# TIA2_4ch.net
KiCad netlist of a schematic drawn in EAGLE
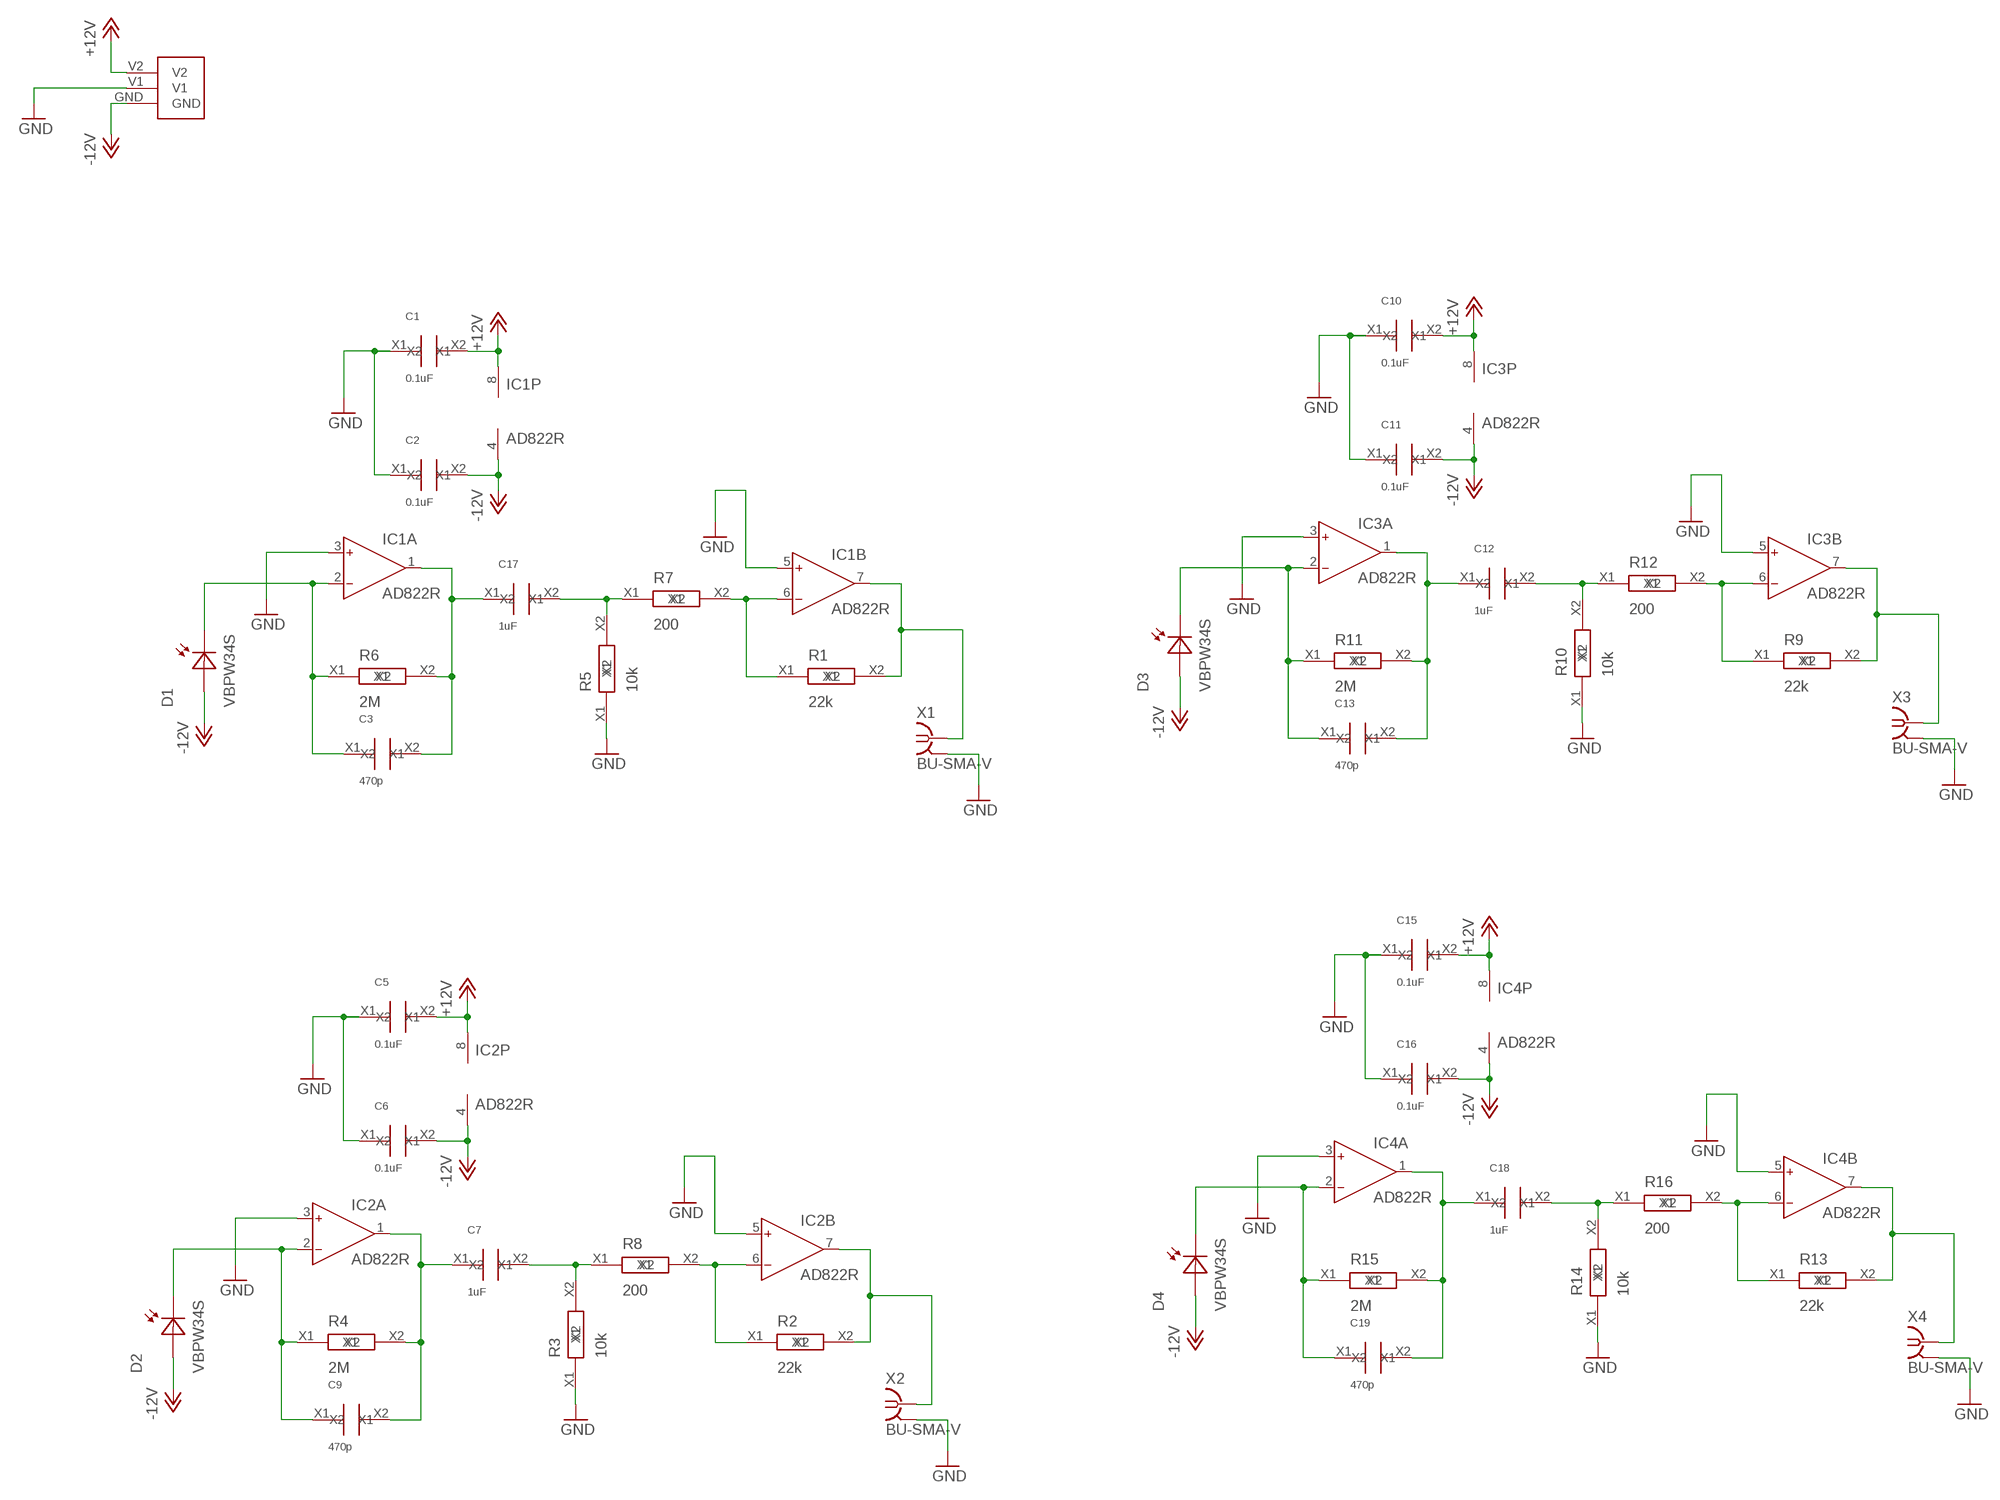
[diagram p0: schematic, sheet 1]

(export (version "E")
  (design (tool "Eeschema 10.0.6"))
  (components
    (comp (ref "C1")
      (value "0.1uF")
      (footprint "eagle-import:SMD_2.1X1.25")
      (libsource (lib "eagle-import") (part "C_SMD_2.1X1.25"))
    )
    (comp (ref "C2")
      (value "0.1uF")
      (footprint "eagle-import:SMD_2.1X1.25")
      (libsource (lib "eagle-import") (part "C_SMD_2.1X1.25"))
    )
    (comp (ref "C3")
      (value "470p")
      (footprint "eagle-import:SMD_2.1X1.25")
      (libsource (lib "eagle-import") (part "C_SMD_2.1X1.25"))
    )
    (comp (ref "C5")
      (value "0.1uF")
      (footprint "eagle-import:SMD_2.1X1.25")
      (libsource (lib "eagle-import") (part "C_SMD_2.1X1.25"))
    )
    (comp (ref "C6")
      (value "0.1uF")
      (footprint "eagle-import:SMD_2.1X1.25")
      (libsource (lib "eagle-import") (part "C_SMD_2.1X1.25"))
    )
    (comp (ref "C7")
      (value "1uF")
      (footprint "eagle-import:SMD_2.1X1.25")
      (libsource (lib "eagle-import") (part "C_SMD_2.1X1.25"))
    )
    (comp (ref "C9")
      (value "470p")
      (footprint "eagle-import:SMD_2.1X1.25")
      (libsource (lib "eagle-import") (part "C_SMD_2.1X1.25"))
    )
    (comp (ref "C10")
      (value "0.1uF")
      (footprint "eagle-import:SMD_2.1X1.25")
      (libsource (lib "eagle-import") (part "C_SMD_2.1X1.25"))
    )
    (comp (ref "C11")
      (value "0.1uF")
      (footprint "eagle-import:SMD_2.1X1.25")
      (libsource (lib "eagle-import") (part "C_SMD_2.1X1.25"))
    )
    (comp (ref "C12")
      (value "1uF")
      (footprint "eagle-import:SMD_2.1X1.25")
      (libsource (lib "eagle-import") (part "C_SMD_2.1X1.25"))
    )
    (comp (ref "C13")
      (value "470p")
      (footprint "eagle-import:SMD_2.1X1.25")
      (libsource (lib "eagle-import") (part "C_SMD_2.1X1.25"))
    )
    (comp (ref "C15")
      (value "0.1uF")
      (footprint "eagle-import:SMD_2.1X1.25")
      (libsource (lib "eagle-import") (part "C_SMD_2.1X1.25"))
    )
    (comp (ref "C16")
      (value "0.1uF")
      (footprint "eagle-import:SMD_2.1X1.25")
      (libsource (lib "eagle-import") (part "C_SMD_2.1X1.25"))
    )
    (comp (ref "C17")
      (value "1uF")
      (footprint "eagle-import:SMD_2.1X1.25")
      (libsource (lib "eagle-import") (part "C_SMD_2.1X1.25"))
    )
    (comp (ref "C18")
      (value "1uF")
      (footprint "eagle-import:SMD_2.1X1.25")
      (libsource (lib "eagle-import") (part "C_SMD_2.1X1.25"))
    )
    (comp (ref "C19")
      (value "470p")
      (footprint "eagle-import:SMD_2.1X1.25")
      (libsource (lib "eagle-import") (part "C_SMD_2.1X1.25"))
    )
    (comp (ref "D1")
      (value "VBPW34S")
      (footprint "eagle-import:SOD6439X130N")
      (fields (field (name "DIGI-KEY_PART_NUMBER") "751-1500-1-ND") (field (name "MF") "Vishay"))
      (libsource (lib "eagle-import") (part "VBPW34S"))
    )
    (comp (ref "D2")
      (value "VBPW34S")
      (footprint "eagle-import:SOD6439X130N")
      (fields (field (name "DIGI-KEY_PART_NUMBER") "751-1500-1-ND") (field (name "MF") "Vishay"))
      (libsource (lib "eagle-import") (part "VBPW34S"))
    )
    (comp (ref "D3")
      (value "VBPW34S")
      (footprint "eagle-import:SOD6439X130N")
      (fields (field (name "DIGI-KEY_PART_NUMBER") "751-1500-1-ND") (field (name "MF") "Vishay"))
      (libsource (lib "eagle-import") (part "VBPW34S"))
    )
    (comp (ref "D4")
      (value "VBPW34S")
      (footprint "eagle-import:SOD6439X130N")
      (fields (field (name "DIGI-KEY_PART_NUMBER") "751-1500-1-ND") (field (name "MF") "Vishay"))
      (libsource (lib "eagle-import") (part "VBPW34S"))
    )
    (comp (ref "IC1")
      (value "AD822R")
      (footprint "eagle-import:SO8")
      (fields (field (name "MF") "ANALOG DEVICES") (field (name "MPN") "AD822BRZ"))
      (libsource (lib "eagle-import") (part "AD822R"))
    )
    (comp (ref "IC2")
      (value "AD822R")
      (footprint "eagle-import:SO8")
      (fields (field (name "MF") "ANALOG DEVICES") (field (name "MPN") "AD822BRZ"))
      (libsource (lib "eagle-import") (part "AD822R"))
    )
    (comp (ref "IC3")
      (value "AD822R")
      (footprint "eagle-import:SO8")
      (fields (field (name "MF") "ANALOG DEVICES") (field (name "MPN") "AD822BRZ"))
      (libsource (lib "eagle-import") (part "AD822R"))
    )
    (comp (ref "IC4")
      (value "AD822R")
      (footprint "eagle-import:SO8")
      (fields (field (name "MF") "ANALOG DEVICES") (field (name "MPN") "AD822BRZ"))
      (libsource (lib "eagle-import") (part "AD822R"))
    )
    (comp (ref "R1")
      (value "22k")
      (footprint "eagle-import:SMD_2.1X1.25")
      (libsource (lib "eagle-import") (part "R_SMD_2.1X1.25"))
    )
    (comp (ref "R2")
      (value "22k")
      (footprint "eagle-import:SMD_2.1X1.25")
      (libsource (lib "eagle-import") (part "R_SMD_2.1X1.25"))
    )
    (comp (ref "R3")
      (value "10k")
      (footprint "eagle-import:SMD_2.1X1.25")
      (libsource (lib "eagle-import") (part "R_SMD_2.1X1.25"))
    )
    (comp (ref "R4")
      (value "2M")
      (footprint "eagle-import:SMD_2.1X1.25")
      (libsource (lib "eagle-import") (part "R_SMD_2.1X1.25"))
    )
    (comp (ref "R5")
      (value "10k")
      (footprint "eagle-import:SMD_2.1X1.25")
      (libsource (lib "eagle-import") (part "R_SMD_2.1X1.25"))
    )
    (comp (ref "R6")
      (value "2M")
      (footprint "eagle-import:SMD_2.1X1.25")
      (libsource (lib "eagle-import") (part "R_SMD_2.1X1.25"))
    )
    (comp (ref "R7")
      (value "200")
      (footprint "eagle-import:SMD_2.1X1.25")
      (libsource (lib "eagle-import") (part "R_SMD_2.1X1.25"))
    )
    (comp (ref "R8")
      (value "200")
      (footprint "eagle-import:SMD_2.1X1.25")
      (libsource (lib "eagle-import") (part "R_SMD_2.1X1.25"))
    )
    (comp (ref "R9")
      (value "22k")
      (footprint "eagle-import:SMD_2.1X1.25")
      (libsource (lib "eagle-import") (part "R_SMD_2.1X1.25"))
    )
    (comp (ref "R10")
      (value "10k")
      (footprint "eagle-import:SMD_2.1X1.25")
      (libsource (lib "eagle-import") (part "R_SMD_2.1X1.25"))
    )
    (comp (ref "R11")
      (value "2M")
      (footprint "eagle-import:SMD_2.1X1.25")
      (libsource (lib "eagle-import") (part "R_SMD_2.1X1.25"))
    )
    (comp (ref "R12")
      (value "200")
      (footprint "eagle-import:SMD_2.1X1.25")
      (libsource (lib "eagle-import") (part "R_SMD_2.1X1.25"))
    )
    (comp (ref "R13")
      (value "22k")
      (footprint "eagle-import:SMD_2.1X1.25")
      (libsource (lib "eagle-import") (part "R_SMD_2.1X1.25"))
    )
    (comp (ref "R14")
      (value "10k")
      (footprint "eagle-import:SMD_2.1X1.25")
      (libsource (lib "eagle-import") (part "R_SMD_2.1X1.25"))
    )
    (comp (ref "R15")
      (value "2M")
      (footprint "eagle-import:SMD_2.1X1.25")
      (libsource (lib "eagle-import") (part "R_SMD_2.1X1.25"))
    )
    (comp (ref "R16")
      (value "200")
      (footprint "eagle-import:SMD_2.1X1.25")
      (libsource (lib "eagle-import") (part "R_SMD_2.1X1.25"))
    )
    (comp (ref "U$1")
      (value "BAT3_PLUG")
      (footprint "eagle-import:BAT3_PLUG")
      (libsource (lib "eagle-import") (part "BAT3_PLUG"))
    )
    (comp (ref "X1")
      (value "BU-SMA-V")
      (footprint "eagle-import:BU-SMA-V")
      (libsource (lib "eagle-import") (part "BU-SMA-V"))
    )
    (comp (ref "X2")
      (value "BU-SMA-V")
      (footprint "eagle-import:BU-SMA-V")
      (libsource (lib "eagle-import") (part "BU-SMA-V"))
    )
    (comp (ref "X3")
      (value "BU-SMA-V")
      (footprint "eagle-import:BU-SMA-V")
      (libsource (lib "eagle-import") (part "BU-SMA-V"))
    )
    (comp (ref "X4")
      (value "BU-SMA-V")
      (footprint "eagle-import:BU-SMA-V")
      (libsource (lib "eagle-import") (part "BU-SMA-V"))
    )
  )
  (nets
    (net (code "1") (name "+12V") (class "Default")
      (node (ref "C1") (pin "X2") (pinfunction "X2_X2") (pintype "bidirectional"))
      (node (ref "C10") (pin "X2") (pinfunction "X2_X2") (pintype "bidirectional"))
      (node (ref "C15") (pin "X2") (pinfunction "X2_X2") (pintype "bidirectional"))
      (node (ref "C5") (pin "X2") (pinfunction "X2_X2") (pintype "bidirectional"))
      (node (ref "IC1") (pin "8") (pinfunction "V+_8") (pintype "power_in"))
      (node (ref "IC2") (pin "8") (pinfunction "V+_8") (pintype "power_in"))
      (node (ref "IC3") (pin "8") (pinfunction "V+_8") (pintype "power_in"))
      (node (ref "IC4") (pin "8") (pinfunction "V+_8") (pintype "power_in"))
      (node (ref "U$1") (pin "V2") (pinfunction "V2_V2") (pintype "bidirectional"))
    )
    (net (code "2") (name "-12V") (class "Default")
      (node (ref "C11") (pin "X2") (pinfunction "X2_X2") (pintype "bidirectional"))
      (node (ref "C16") (pin "X2") (pinfunction "X2_X2") (pintype "bidirectional"))
      (node (ref "C2") (pin "X2") (pinfunction "X2_X2") (pintype "bidirectional"))
      (node (ref "C6") (pin "X2") (pinfunction "X2_X2") (pintype "bidirectional"))
      (node (ref "D1") (pin "A") (pinfunction "A_A") (pintype "passive"))
      (node (ref "D2") (pin "A") (pinfunction "A_A") (pintype "passive"))
      (node (ref "D3") (pin "A") (pinfunction "A_A") (pintype "passive"))
      (node (ref "D4") (pin "A") (pinfunction "A_A") (pintype "passive"))
      (node (ref "IC1") (pin "4") (pinfunction "V-_4") (pintype "power_in"))
      (node (ref "IC2") (pin "4") (pinfunction "V-_4") (pintype "power_in"))
      (node (ref "IC3") (pin "4") (pinfunction "V-_4") (pintype "power_in"))
      (node (ref "IC4") (pin "4") (pinfunction "V-_4") (pintype "power_in"))
      (node (ref "U$1") (pin "GND") (pinfunction "GND_GND") (pintype "bidirectional"))
    )
    (net (code "3") (name "GND") (class "Default")
      (node (ref "C1") (pin "X1") (pinfunction "X1_X1") (pintype "bidirectional"))
      (node (ref "C10") (pin "X1") (pinfunction "X1_X1") (pintype "bidirectional"))
      (node (ref "C11") (pin "X1") (pinfunction "X1_X1") (pintype "bidirectional"))
      (node (ref "C15") (pin "X1") (pinfunction "X1_X1") (pintype "bidirectional"))
      (node (ref "C16") (pin "X1") (pinfunction "X1_X1") (pintype "bidirectional"))
      (node (ref "C2") (pin "X1") (pinfunction "X1_X1") (pintype "bidirectional"))
      (node (ref "C5") (pin "X1") (pinfunction "X1_X1") (pintype "bidirectional"))
      (node (ref "C6") (pin "X1") (pinfunction "X1_X1") (pintype "bidirectional"))
      (node (ref "IC1") (pin "3") (pinfunction "IN+_3") (pintype "input"))
      (node (ref "IC1") (pin "5") (pinfunction "IN+_5") (pintype "input"))
      (node (ref "IC2") (pin "3") (pinfunction "IN+_3") (pintype "input"))
      (node (ref "IC2") (pin "5") (pinfunction "IN+_5") (pintype "input"))
      (node (ref "IC3") (pin "3") (pinfunction "IN+_3") (pintype "input"))
      (node (ref "IC3") (pin "5") (pinfunction "IN+_5") (pintype "input"))
      (node (ref "IC4") (pin "3") (pinfunction "IN+_3") (pintype "input"))
      (node (ref "IC4") (pin "5") (pinfunction "IN+_5") (pintype "input"))
      (node (ref "R10") (pin "X1") (pinfunction "X1_X1") (pintype "bidirectional"))
      (node (ref "R14") (pin "X1") (pinfunction "X1_X1") (pintype "bidirectional"))
      (node (ref "R3") (pin "X1") (pinfunction "X1_X1") (pintype "bidirectional"))
      (node (ref "R5") (pin "X1") (pinfunction "X1_X1") (pintype "bidirectional"))
      (node (ref "U$1") (pin "V1") (pinfunction "V1_V1") (pintype "bidirectional"))
      (node (ref "X1") (pin "2") (pinfunction "2_2") (pintype "passive"))
      (node (ref "X1") (pin "3") (pinfunction "2_3") (pintype "passive"))
      (node (ref "X1") (pin "4") (pinfunction "2_4") (pintype "passive"))
      (node (ref "X1") (pin "5") (pinfunction "2_5") (pintype "passive"))
      (node (ref "X2") (pin "2") (pinfunction "2_2") (pintype "passive"))
      (node (ref "X2") (pin "3") (pinfunction "2_3") (pintype "passive"))
      (node (ref "X2") (pin "4") (pinfunction "2_4") (pintype "passive"))
      (node (ref "X2") (pin "5") (pinfunction "2_5") (pintype "passive"))
      (node (ref "X3") (pin "2") (pinfunction "2_2") (pintype "passive"))
      (node (ref "X3") (pin "3") (pinfunction "2_3") (pintype "passive"))
      (node (ref "X3") (pin "4") (pinfunction "2_4") (pintype "passive"))
      (node (ref "X3") (pin "5") (pinfunction "2_5") (pintype "passive"))
      (node (ref "X4") (pin "2") (pinfunction "2_2") (pintype "passive"))
      (node (ref "X4") (pin "3") (pinfunction "2_3") (pintype "passive"))
      (node (ref "X4") (pin "4") (pinfunction "2_4") (pintype "passive"))
      (node (ref "X4") (pin "5") (pinfunction "2_5") (pintype "passive"))
    )
    (net (code "4") (name "Net-(C7-PadX2)") (class "Default")
      (node (ref "C7") (pin "X2") (pinfunction "X2_X2") (pintype "bidirectional"))
      (node (ref "R3") (pin "X2") (pinfunction "X2_X2") (pintype "bidirectional"))
      (node (ref "R8") (pin "X1") (pinfunction "X1_X1") (pintype "bidirectional"))
    )
    (net (code "5") (name "Net-(C12-PadX2)") (class "Default")
      (node (ref "C12") (pin "X2") (pinfunction "X2_X2") (pintype "bidirectional"))
      (node (ref "R10") (pin "X2") (pinfunction "X2_X2") (pintype "bidirectional"))
      (node (ref "R12") (pin "X1") (pinfunction "X1_X1") (pintype "bidirectional"))
    )
    (net (code "6") (name "Net-(C17-PadX2)") (class "Default")
      (node (ref "C17") (pin "X2") (pinfunction "X2_X2") (pintype "bidirectional"))
      (node (ref "R5") (pin "X2") (pinfunction "X2_X2") (pintype "bidirectional"))
      (node (ref "R7") (pin "X1") (pinfunction "X1_X1") (pintype "bidirectional"))
    )
    (net (code "7") (name "Net-(C18-PadX2)") (class "Default")
      (node (ref "C18") (pin "X2") (pinfunction "X2_X2") (pintype "bidirectional"))
      (node (ref "R14") (pin "X2") (pinfunction "X2_X2") (pintype "bidirectional"))
      (node (ref "R16") (pin "X1") (pinfunction "X1_X1") (pintype "bidirectional"))
    )
    (net (code "8") (name "Net-(IC1A-IN-)") (class "Default")
      (node (ref "C3") (pin "X1") (pinfunction "X1_X1") (pintype "bidirectional"))
      (node (ref "D1") (pin "C") (pinfunction "C_C") (pintype "passive"))
      (node (ref "IC1") (pin "2") (pinfunction "IN-_2") (pintype "input"))
      (node (ref "R6") (pin "X1") (pinfunction "X1_X1") (pintype "bidirectional"))
    )
    (net (code "9") (name "Net-(IC1A-OUT)") (class "Default")
      (node (ref "C17") (pin "X1") (pinfunction "X1_X1") (pintype "bidirectional"))
      (node (ref "C3") (pin "X2") (pinfunction "X2_X2") (pintype "bidirectional"))
      (node (ref "IC1") (pin "1") (pinfunction "OUT_1") (pintype "output"))
      (node (ref "R6") (pin "X2") (pinfunction "X2_X2") (pintype "bidirectional"))
    )
    (net (code "10") (name "Net-(IC1B-IN-)") (class "Default")
      (node (ref "IC1") (pin "6") (pinfunction "IN-_6") (pintype "input"))
      (node (ref "R1") (pin "X1") (pinfunction "X1_X1") (pintype "bidirectional"))
      (node (ref "R7") (pin "X2") (pinfunction "X2_X2") (pintype "bidirectional"))
    )
    (net (code "11") (name "Net-(IC1B-OUT)") (class "Default")
      (node (ref "IC1") (pin "7") (pinfunction "OUT_7") (pintype "output"))
      (node (ref "R1") (pin "X2") (pinfunction "X2_X2") (pintype "bidirectional"))
      (node (ref "X1") (pin "1") (pinfunction "1_1") (pintype "passive"))
    )
    (net (code "12") (name "Net-(IC2A-IN-)") (class "Default")
      (node (ref "C9") (pin "X1") (pinfunction "X1_X1") (pintype "bidirectional"))
      (node (ref "D2") (pin "C") (pinfunction "C_C") (pintype "passive"))
      (node (ref "IC2") (pin "2") (pinfunction "IN-_2") (pintype "input"))
      (node (ref "R4") (pin "X1") (pinfunction "X1_X1") (pintype "bidirectional"))
    )
    (net (code "13") (name "Net-(IC2A-OUT)") (class "Default")
      (node (ref "C7") (pin "X1") (pinfunction "X1_X1") (pintype "bidirectional"))
      (node (ref "C9") (pin "X2") (pinfunction "X2_X2") (pintype "bidirectional"))
      (node (ref "IC2") (pin "1") (pinfunction "OUT_1") (pintype "output"))
      (node (ref "R4") (pin "X2") (pinfunction "X2_X2") (pintype "bidirectional"))
    )
    (net (code "14") (name "Net-(IC2B-IN-)") (class "Default")
      (node (ref "IC2") (pin "6") (pinfunction "IN-_6") (pintype "input"))
      (node (ref "R2") (pin "X1") (pinfunction "X1_X1") (pintype "bidirectional"))
      (node (ref "R8") (pin "X2") (pinfunction "X2_X2") (pintype "bidirectional"))
    )
    (net (code "15") (name "Net-(IC2B-OUT)") (class "Default")
      (node (ref "IC2") (pin "7") (pinfunction "OUT_7") (pintype "output"))
      (node (ref "R2") (pin "X2") (pinfunction "X2_X2") (pintype "bidirectional"))
      (node (ref "X2") (pin "1") (pinfunction "1_1") (pintype "passive"))
    )
    (net (code "16") (name "Net-(IC3A-IN-)") (class "Default")
      (node (ref "C13") (pin "X1") (pinfunction "X1_X1") (pintype "bidirectional"))
      (node (ref "D3") (pin "C") (pinfunction "C_C") (pintype "passive"))
      (node (ref "IC3") (pin "2") (pinfunction "IN-_2") (pintype "input"))
      (node (ref "R11") (pin "X1") (pinfunction "X1_X1") (pintype "bidirectional"))
    )
    (net (code "17") (name "Net-(IC3A-OUT)") (class "Default")
      (node (ref "C12") (pin "X1") (pinfunction "X1_X1") (pintype "bidirectional"))
      (node (ref "C13") (pin "X2") (pinfunction "X2_X2") (pintype "bidirectional"))
      (node (ref "IC3") (pin "1") (pinfunction "OUT_1") (pintype "output"))
      (node (ref "R11") (pin "X2") (pinfunction "X2_X2") (pintype "bidirectional"))
    )
    (net (code "18") (name "Net-(IC3B-IN-)") (class "Default")
      (node (ref "IC3") (pin "6") (pinfunction "IN-_6") (pintype "input"))
      (node (ref "R12") (pin "X2") (pinfunction "X2_X2") (pintype "bidirectional"))
      (node (ref "R9") (pin "X1") (pinfunction "X1_X1") (pintype "bidirectional"))
    )
    (net (code "19") (name "Net-(IC3B-OUT)") (class "Default")
      (node (ref "IC3") (pin "7") (pinfunction "OUT_7") (pintype "output"))
      (node (ref "R9") (pin "X2") (pinfunction "X2_X2") (pintype "bidirectional"))
      (node (ref "X3") (pin "1") (pinfunction "1_1") (pintype "passive"))
    )
    (net (code "20") (name "Net-(IC4A-IN-)") (class "Default")
      (node (ref "C19") (pin "X1") (pinfunction "X1_X1") (pintype "bidirectional"))
      (node (ref "D4") (pin "C") (pinfunction "C_C") (pintype "passive"))
      (node (ref "IC4") (pin "2") (pinfunction "IN-_2") (pintype "input"))
      (node (ref "R15") (pin "X1") (pinfunction "X1_X1") (pintype "bidirectional"))
    )
    (net (code "21") (name "Net-(IC4A-OUT)") (class "Default")
      (node (ref "C18") (pin "X1") (pinfunction "X1_X1") (pintype "bidirectional"))
      (node (ref "C19") (pin "X2") (pinfunction "X2_X2") (pintype "bidirectional"))
      (node (ref "IC4") (pin "1") (pinfunction "OUT_1") (pintype "output"))
      (node (ref "R15") (pin "X2") (pinfunction "X2_X2") (pintype "bidirectional"))
    )
    (net (code "22") (name "Net-(IC4B-IN-)") (class "Default")
      (node (ref "IC4") (pin "6") (pinfunction "IN-_6") (pintype "input"))
      (node (ref "R13") (pin "X1") (pinfunction "X1_X1") (pintype "bidirectional"))
      (node (ref "R16") (pin "X2") (pinfunction "X2_X2") (pintype "bidirectional"))
    )
    (net (code "23") (name "Net-(IC4B-OUT)") (class "Default")
      (node (ref "IC4") (pin "7") (pinfunction "OUT_7") (pintype "output"))
      (node (ref "R13") (pin "X2") (pinfunction "X2_X2") (pintype "bidirectional"))
      (node (ref "X4") (pin "1") (pinfunction "1_1") (pintype "passive"))
    )
  )
)
